# basic-maschinen.net
KiCad netlist of a schematic drawn in EAGLE
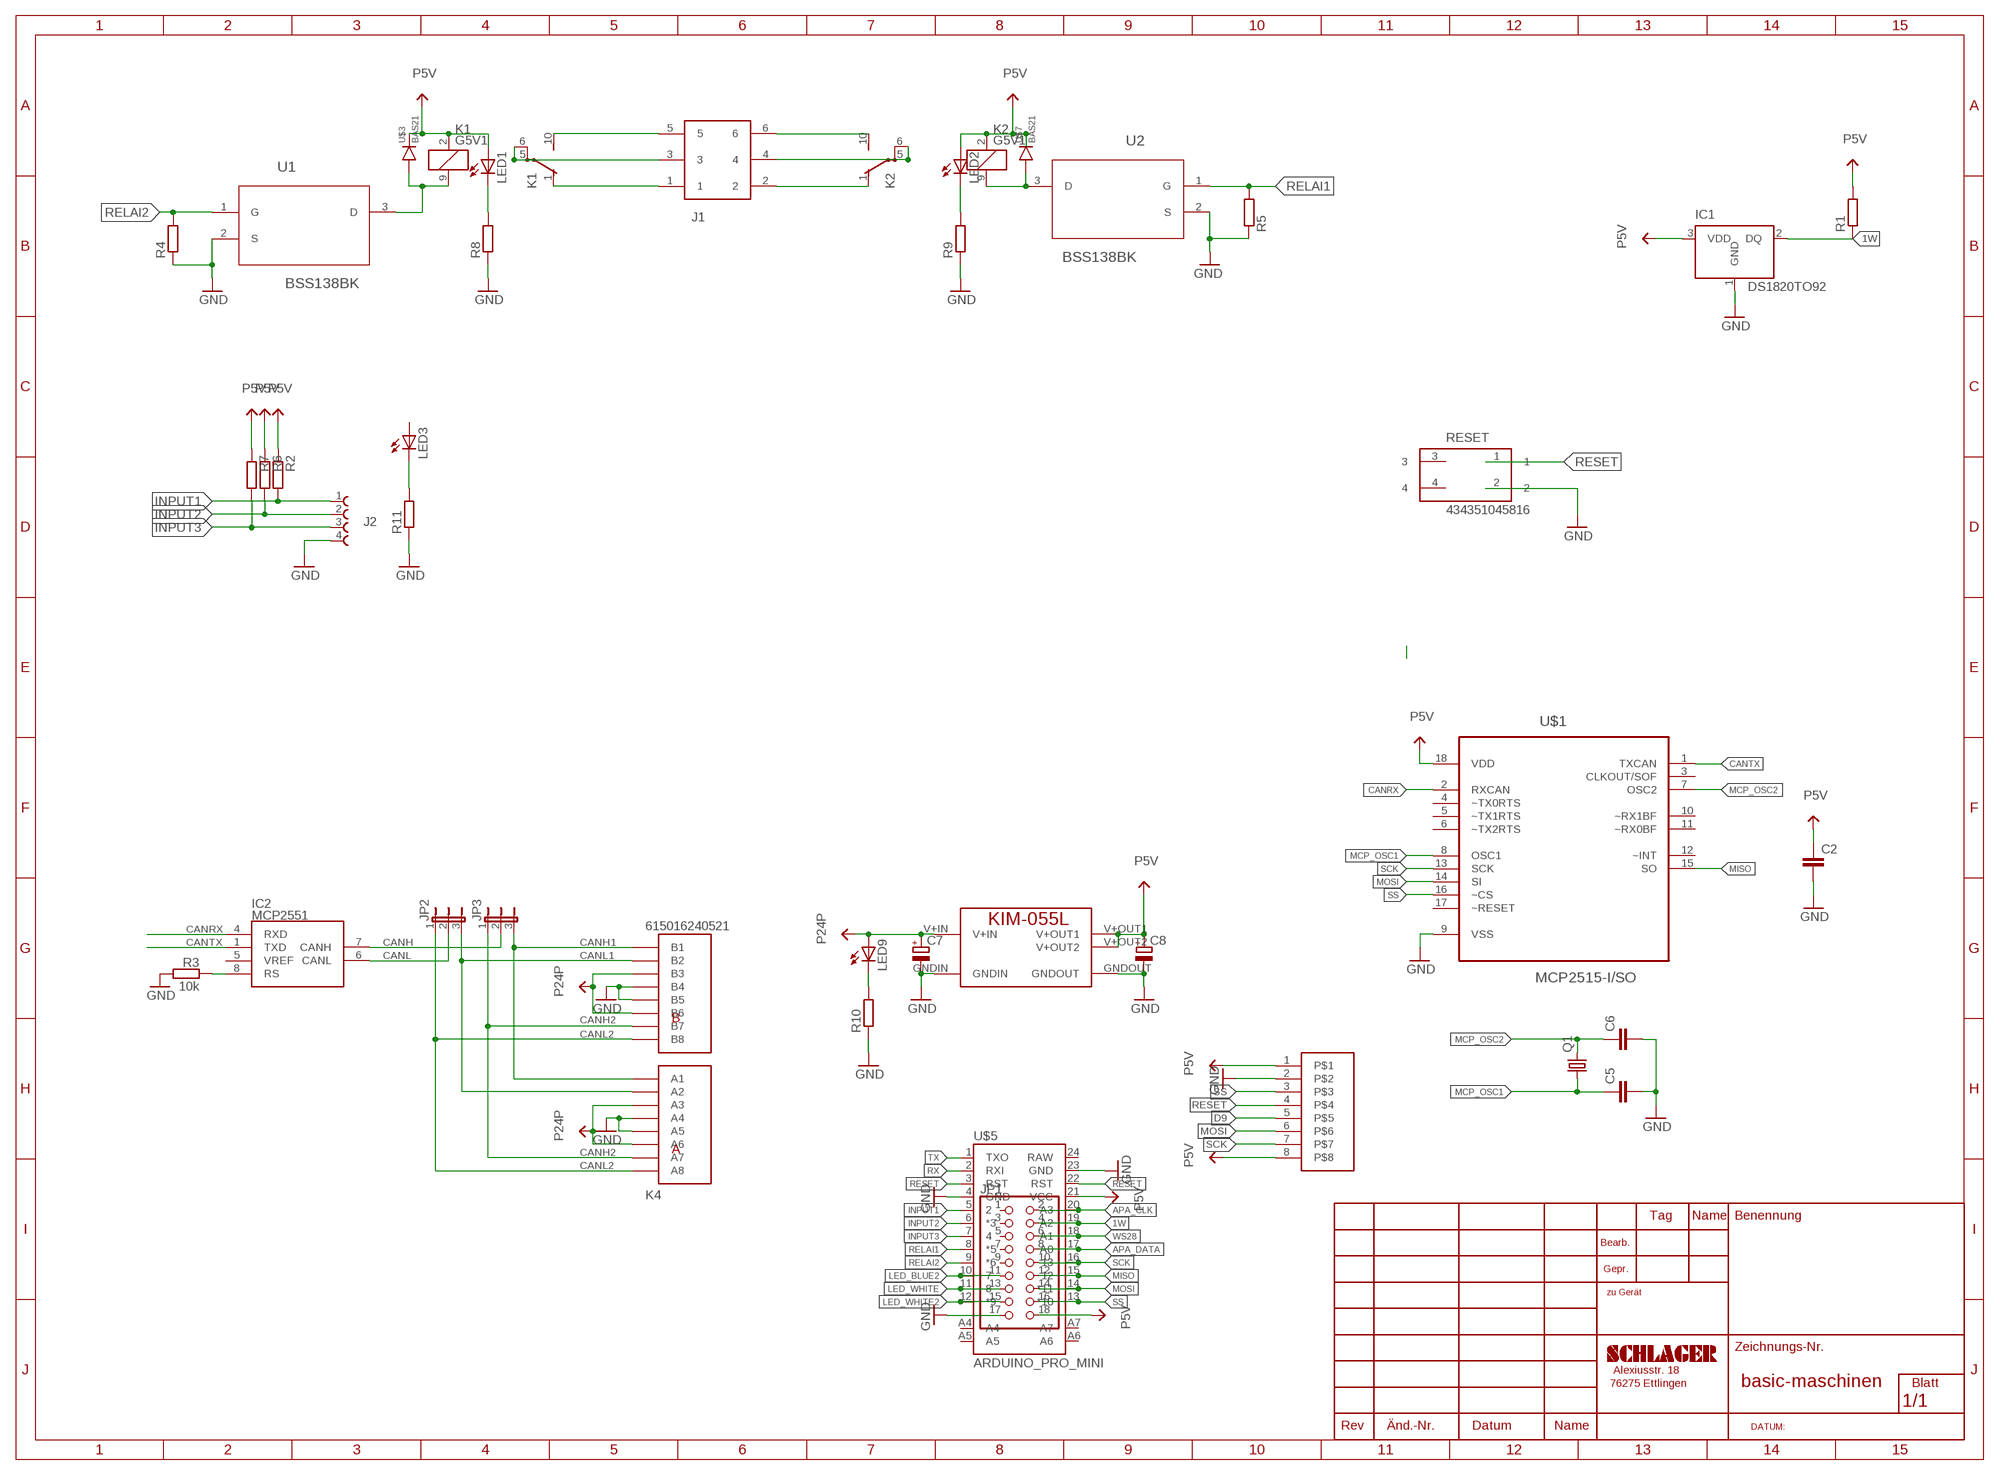
[diagram p0: schematic, sheet 1]

(export (version "E")
  (design (tool "Eeschema 10.0.6"))
  (components
    (comp (ref "C2")
      (value "C-EUC0805")
      (footprint "eagle-import:C0805")
      (libsource (lib "eagle-import") (part "C-EUC0805"))
    )
    (comp (ref "C5")
      (value "C-EUC0805")
      (footprint "eagle-import:C0805")
      (libsource (lib "eagle-import") (part "C-EUC0805"))
    )
    (comp (ref "C6")
      (value "C-EUC0805")
      (footprint "eagle-import:C0805")
      (libsource (lib "eagle-import") (part "C-EUC0805"))
    )
    (comp (ref "C7")
      (value "CPOL-EUE5-10.5")
      (footprint "eagle-import:E5-10,5")
      (libsource (lib "eagle-import") (part "CPOL-EUE5-10.5"))
    )
    (comp (ref "C8")
      (value "CPOL-EUE5-10.5")
      (footprint "eagle-import:E5-10,5")
      (libsource (lib "eagle-import") (part "CPOL-EUE5-10.5"))
    )
    (comp (ref "IC1")
      (value "DS1820TO92")
      (footprint "eagle-import:TO-92")
      (libsource (lib "eagle-import") (part "DS1820TO92"))
    )
    (comp (ref "IC2")
      (value "MCP2551")
      (footprint "eagle-import:SO-8")
      (libsource (lib "eagle-import") (part "MCP2551"))
    )
    (comp (ref "J1")
      (value "691327310006")
      (footprint "eagle-import:691327310006")
      (libsource (lib "eagle-import") (part "691327310006"))
    )
    (comp (ref "J2")
      (value "691322310004")
      (footprint "eagle-import:691322310004")
      (libsource (lib "eagle-import") (part "691322310004"))
    )
    (comp (ref "JP1")
      (value "PINHD-2X9")
      (footprint "eagle-import:2X09")
      (libsource (lib "eagle-import") (part "PINHD-2X9"))
    )
    (comp (ref "JP2")
      (value "JP2E")
      (footprint "eagle-import:JP2")
      (libsource (lib "eagle-import") (part "JP2E"))
    )
    (comp (ref "JP3")
      (value "JP2E")
      (footprint "eagle-import:JP2")
      (libsource (lib "eagle-import") (part "JP2E"))
    )
    (comp (ref "K1")
      (value "G5V1")
      (footprint "eagle-import:G5V1")
      (fields (field (name "MPN") "G5V-1-DC24"))
      (libsource (lib "eagle-import") (part "G5V1"))
    )
    (comp (ref "K2")
      (value "G5V1")
      (footprint "eagle-import:G5V1")
      (fields (field (name "MPN") "G5V-1-DC24"))
      (libsource (lib "eagle-import") (part "G5V1"))
    )
    (comp (ref "K4")
      (value "615016240521")
      (footprint "eagle-import:615016240521")
      (libsource (lib "eagle-import") (part "615016240521"))
    )
    (comp (ref "LED1")
      (value "LED3MM")
      (footprint "eagle-import:LED3MM")
      (libsource (lib "eagle-import") (part "LED3MM"))
    )
    (comp (ref "LED2")
      (value "LED3MM")
      (footprint "eagle-import:LED3MM")
      (libsource (lib "eagle-import") (part "LED3MM"))
    )
    (comp (ref "LED3")
      (value "LED3MM")
      (footprint "eagle-import:LED3MM")
      (libsource (lib "eagle-import") (part "LED3MM"))
    )
    (comp (ref "LED9")
      (value "LED3MM")
      (footprint "eagle-import:LED3MM")
      (libsource (lib "eagle-import") (part "LED3MM"))
    )
    (comp (ref "MOD1")
      (value "KIM-055L")
      (footprint "eagle-import:KIM-055L")
      (libsource (lib "eagle-import") (part "KIM-055L"))
    )
    (comp (ref "Q1")
      (value "CRYSTALHC49S")
      (footprint "eagle-import:HC49_S")
      (libsource (lib "eagle-import") (part "CRYSTALHC49S"))
    )
    (comp (ref "R1")
      (value "R-EU_M0805")
      (footprint "eagle-import:M0805")
      (libsource (lib "eagle-import") (part "schlager_passiv_R-EU_M0805"))
    )
    (comp (ref "R2")
      (value "R-EU_M0805")
      (footprint "eagle-import:M0805")
      (libsource (lib "eagle-import") (part "schlager_passiv_R-EU_M0805"))
    )
    (comp (ref "R3")
      (value "10k")
      (footprint "eagle-import:R0603")
      (libsource (lib "eagle-import") (part "R-EU_R0603"))
    )
    (comp (ref "R4")
      (value "R-EU_M0805")
      (footprint "eagle-import:M0805")
      (libsource (lib "eagle-import") (part "schlager_passiv_R-EU_M0805"))
    )
    (comp (ref "R5")
      (value "R-EU_M0805")
      (footprint "eagle-import:M0805")
      (libsource (lib "eagle-import") (part "schlager_passiv_R-EU_M0805"))
    )
    (comp (ref "R6")
      (value "R-EU_M0805")
      (footprint "eagle-import:M0805")
      (libsource (lib "eagle-import") (part "schlager_passiv_R-EU_M0805"))
    )
    (comp (ref "R7")
      (value "R-EU_M0805")
      (footprint "eagle-import:M0805")
      (libsource (lib "eagle-import") (part "schlager_passiv_R-EU_M0805"))
    )
    (comp (ref "R8")
      (value "R-EU_R0805")
      (footprint "eagle-import:R0805")
      (libsource (lib "eagle-import") (part "schlager_passiv_R-EU_R0805"))
    )
    (comp (ref "R9")
      (value "R-EU_R0805")
      (footprint "eagle-import:R0805")
      (libsource (lib "eagle-import") (part "schlager_passiv_R-EU_R0805"))
    )
    (comp (ref "R10")
      (value "R-EU_R0805")
      (footprint "eagle-import:R0805")
      (libsource (lib "eagle-import") (part "schlager_passiv_R-EU_R0805"))
    )
    (comp (ref "R11")
      (value "R-EU_R0805")
      (footprint "eagle-import:R0805")
      (libsource (lib "eagle-import") (part "schlager_passiv_R-EU_R0805"))
    )
    (comp (ref "RESET")
      (value "434351045816")
      (footprint "eagle-import:434351045816")
      (libsource (lib "eagle-import") (part "434351045816"))
    )
    (comp (ref "U$1")
      (value "MCP2515-I/SO")
      (footprint "eagle-import:SOIC127P1034X264-18N")
      (libsource (lib "eagle-import") (part "MCP2515-I/SO"))
    )
    (comp (ref "U$3")
      (value "BAS21")
      (footprint "eagle-import:SOT23")
      (libsource (lib "eagle-import") (part "BAS21"))
    )
    (comp (ref "U$4")
      (value "1.44-128X128")
      (footprint "eagle-import:1.44-128X128")
      (libsource (lib "eagle-import") (part "1.44-128X128"))
    )
    (comp (ref "U$5")
      (value "ARDUINO_PRO_MINI")
      (footprint "eagle-import:ARDUINO_PRO_MINI")
      (libsource (lib "eagle-import") (part "ARDUINO_PRO_MINI"))
    )
    (comp (ref "U$7")
      (value "BAS21")
      (footprint "eagle-import:SOT23")
      (libsource (lib "eagle-import") (part "BAS21"))
    )
    (comp (ref "U1")
      (value "BSS138BK")
      (footprint "eagle-import:SOT65P210X110-3N")
      (libsource (lib "eagle-import") (part "BSS138BK"))
    )
    (comp (ref "U2")
      (value "BSS138BK")
      (footprint "eagle-import:SOT65P210X110-3N")
      (libsource (lib "eagle-import") (part "BSS138BK"))
    )
  )
  (nets
    (net (code "1") (name "/CANH") (class "Default")
      (node (ref "IC2") (pin "7") (pinfunction "CANH_7") (pintype "bidirectional"))
      (node (ref "JP3") (pin "2") (pinfunction "2_2") (pintype "passive"))
    )
    (net (code "2") (name "/CANH1") (class "Default")
      (node (ref "JP3") (pin "3") (pinfunction "3_3") (pintype "passive"))
      (node (ref "K4") (pin "A1") (pinfunction "A1_A1") (pintype "passive"))
      (node (ref "K4") (pin "B1") (pinfunction "B1_B1") (pintype "passive"))
    )
    (net (code "3") (name "/CANH2") (class "Default")
      (node (ref "JP3") (pin "1") (pinfunction "1_1") (pintype "passive"))
      (node (ref "K4") (pin "A7") (pinfunction "A7_A7") (pintype "passive"))
      (node (ref "K4") (pin "B7") (pinfunction "B7_B7") (pintype "passive"))
    )
    (net (code "4") (name "/CANL") (class "Default")
      (node (ref "IC2") (pin "6") (pinfunction "CANL_6") (pintype "bidirectional"))
      (node (ref "JP2") (pin "2") (pinfunction "2_2") (pintype "passive"))
    )
    (net (code "5") (name "/CANL1") (class "Default")
      (node (ref "JP2") (pin "3") (pinfunction "3_3") (pintype "passive"))
      (node (ref "K4") (pin "A2") (pinfunction "A2_A2") (pintype "passive"))
      (node (ref "K4") (pin "B2") (pinfunction "B2_B2") (pintype "passive"))
    )
    (net (code "6") (name "/CANL2") (class "Default")
      (node (ref "JP2") (pin "1") (pinfunction "1_1") (pintype "passive"))
      (node (ref "K4") (pin "A8") (pinfunction "A8_A8") (pintype "passive"))
      (node (ref "K4") (pin "B8") (pinfunction "B8_B8") (pintype "passive"))
    )
    (net (code "7") (name "1W") (class "Default")
      (node (ref "IC1") (pin "2") (pinfunction "DQ_2") (pintype "output"))
      (node (ref "JP1") (pin "4") (pinfunction "4_4") (pintype "passive"))
      (node (ref "R1") (pin "1") (pinfunction "1_1") (pintype "passive"))
      (node (ref "U$5") (pin "19") (pinfunction "A2_19") (pintype "bidirectional"))
    )
    (net (code "8") (name "APA_CLK") (class "Default")
      (node (ref "JP1") (pin "2") (pinfunction "2_2") (pintype "passive"))
      (node (ref "U$5") (pin "20") (pinfunction "A3_20") (pintype "bidirectional"))
    )
    (net (code "9") (name "APA_DATA") (class "Default")
      (node (ref "JP1") (pin "8") (pinfunction "8_8") (pintype "passive"))
      (node (ref "U$5") (pin "17") (pinfunction "A0_17") (pintype "bidirectional"))
    )
    (net (code "10") (name "CANRX") (class "Default")
      (node (ref "IC2") (pin "4") (pinfunction "RXD_4") (pintype "bidirectional"))
      (node (ref "U$1") (pin "2") (pinfunction "RXCAN_2") (pintype "input"))
    )
    (net (code "11") (name "CANTX") (class "Default")
      (node (ref "IC2") (pin "1") (pinfunction "TXD_1") (pintype "bidirectional"))
      (node (ref "U$1") (pin "1") (pinfunction "TXCAN_1") (pintype "output"))
    )
    (net (code "12") (name "D9") (class "Default")
      (node (ref "U$4") (pin "5") (pinfunction "P$5_5") (pintype "bidirectional"))
    )
    (net (code "13") (name "GND") (class "Default")
      (node (ref "C2") (pin "2") (pinfunction "2_2") (pintype "passive"))
      (node (ref "C5") (pin "2") (pinfunction "2_2") (pintype "passive"))
      (node (ref "C6") (pin "2") (pinfunction "2_2") (pintype "passive"))
      (node (ref "C7") (pin "-") (pinfunction "-_-") (pintype "passive"))
      (node (ref "C8") (pin "-") (pinfunction "-_-") (pintype "passive"))
      (node (ref "IC1") (pin "1") (pinfunction "GND_1") (pintype "power_in"))
      (node (ref "J2") (pin "4") (pinfunction "4_4") (pintype "passive"))
      (node (ref "JP1") (pin "17") (pinfunction "17_17") (pintype "passive"))
      (node (ref "K4") (pin "A4") (pinfunction "A4_A4") (pintype "passive"))
      (node (ref "K4") (pin "A5") (pinfunction "A5_A5") (pintype "passive"))
      (node (ref "K4") (pin "B4") (pinfunction "B4_B4") (pintype "passive"))
      (node (ref "K4") (pin "B5") (pinfunction "B5_B5") (pintype "passive"))
      (node (ref "MOD1") (pin "GNDIN") (pinfunction "GNDIN_GNDIN") (pintype "bidirectional"))
      (node (ref "MOD1") (pin "GNDOUT") (pinfunction "GNDOUT_GNDOUT") (pintype "bidirectional"))
      (node (ref "R10") (pin "1") (pinfunction "1_1") (pintype "passive"))
      (node (ref "R11") (pin "1") (pinfunction "1_1") (pintype "passive"))
      (node (ref "R3") (pin "2") (pinfunction "2_2") (pintype "passive"))
      (node (ref "R4") (pin "1") (pinfunction "1_1") (pintype "passive"))
      (node (ref "R5") (pin "1") (pinfunction "1_1") (pintype "passive"))
      (node (ref "R8") (pin "1") (pinfunction "1_1") (pintype "passive"))
      (node (ref "R9") (pin "1") (pinfunction "1_1") (pintype "passive"))
      (node (ref "RESET") (pin "2") (pinfunction "2_2") (pintype "bidirectional"))
      (node (ref "U$1") (pin "9") (pinfunction "VSS_9") (pintype "power_in"))
      (node (ref "U$4") (pin "2") (pinfunction "P$2_2") (pintype "bidirectional"))
      (node (ref "U$5") (pin "23") (pinfunction "GND_23") (pintype "bidirectional"))
      (node (ref "U$5") (pin "4") (pinfunction "GND_4") (pintype "bidirectional"))
      (node (ref "U1") (pin "2") (pinfunction "S_2") (pintype "passive"))
      (node (ref "U2") (pin "2") (pinfunction "S_2") (pintype "passive"))
    )
    (net (code "14") (name "INPUT1") (class "Default")
      (node (ref "J2") (pin "1") (pinfunction "1_1") (pintype "passive"))
      (node (ref "R2") (pin "2") (pinfunction "2_2") (pintype "passive"))
      (node (ref "U$5") (pin "5") (pinfunction "2_5") (pintype "bidirectional"))
    )
    (net (code "15") (name "INPUT2") (class "Default")
      (node (ref "J2") (pin "2") (pinfunction "2_2") (pintype "passive"))
      (node (ref "R6") (pin "2") (pinfunction "2_2") (pintype "passive"))
      (node (ref "U$5") (pin "6") (pinfunction "*3_6") (pintype "bidirectional"))
    )
    (net (code "16") (name "INPUT3") (class "Default")
      (node (ref "J2") (pin "3") (pinfunction "3_3") (pintype "passive"))
      (node (ref "R7") (pin "2") (pinfunction "2_2") (pintype "passive"))
      (node (ref "U$5") (pin "7") (pinfunction "4_7") (pintype "bidirectional"))
    )
    (net (code "17") (name "LED_BLUE2") (class "Default")
      (node (ref "JP1") (pin "11") (pinfunction "11_11") (pintype "passive"))
      (node (ref "U$5") (pin "10") (pinfunction "7_10") (pintype "bidirectional"))
    )
    (net (code "18") (name "LED_WHITE") (class "Default")
      (node (ref "JP1") (pin "13") (pinfunction "13_13") (pintype "passive"))
      (node (ref "U$5") (pin "11") (pinfunction "8_11") (pintype "bidirectional"))
    )
    (net (code "19") (name "LED_WHITE2") (class "Default")
      (node (ref "JP1") (pin "15") (pinfunction "15_15") (pintype "passive"))
      (node (ref "U$5") (pin "12") (pinfunction "*9_12") (pintype "bidirectional"))
    )
    (net (code "20") (name "MCP_OSC1") (class "Default")
      (node (ref "C5") (pin "1") (pinfunction "1_1") (pintype "passive"))
      (node (ref "Q1") (pin "1") (pinfunction "1_1") (pintype "passive"))
      (node (ref "U$1") (pin "8") (pinfunction "OSC1_8") (pintype "input"))
    )
    (net (code "21") (name "MCP_OSC2") (class "Default")
      (node (ref "C6") (pin "1") (pinfunction "1_1") (pintype "passive"))
      (node (ref "Q1") (pin "2") (pinfunction "2_2") (pintype "passive"))
      (node (ref "U$1") (pin "7") (pinfunction "OSC2_7") (pintype "output"))
    )
    (net (code "22") (name "MISO") (class "Default")
      (node (ref "JP1") (pin "12") (pinfunction "12_12") (pintype "passive"))
      (node (ref "U$1") (pin "15") (pinfunction "SO_15") (pintype "output"))
      (node (ref "U$5") (pin "15") (pinfunction "12_15") (pintype "bidirectional"))
    )
    (net (code "23") (name "MOSI") (class "Default")
      (node (ref "JP1") (pin "14") (pinfunction "14_14") (pintype "passive"))
      (node (ref "U$1") (pin "14") (pinfunction "SI_14") (pintype "input"))
      (node (ref "U$4") (pin "6") (pinfunction "P$6_6") (pintype "bidirectional"))
      (node (ref "U$5") (pin "14") (pinfunction "*11_14") (pintype "bidirectional"))
    )
    (net (code "24") (name "Net-(IC2A-RS)") (class "Default")
      (node (ref "IC2") (pin "8") (pinfunction "RS_8") (pintype "bidirectional"))
      (node (ref "R3") (pin "1") (pinfunction "1_1") (pintype "passive"))
    )
    (net (code "25") (name "Net-(J1-Pad3)") (class "Default")
      (node (ref "J1") (pin "3") (pinfunction "3_3") (pintype "passive"))
      (node (ref "K1") (pin "5") (pinfunction "P_5") (pintype "passive"))
      (node (ref "K1") (pin "6") (pinfunction "P_6") (pintype "passive"))
    )
    (net (code "26") (name "Net-(J1-Pad4)") (class "Default")
      (node (ref "J1") (pin "4") (pinfunction "4_4") (pintype "passive"))
      (node (ref "K2") (pin "5") (pinfunction "P_5") (pintype "passive"))
      (node (ref "K2") (pin "6") (pinfunction "P_6") (pintype "passive"))
    )
    (net (code "27") (name "Net-(K1A-2)") (class "Default")
      (node (ref "K1") (pin "9") (pinfunction "2_9") (pintype "passive"))
      (node (ref "U$3") (pin "1") (pinfunction "A_1") (pintype "bidirectional"))
      (node (ref "U1") (pin "3") (pinfunction "D_3") (pintype "passive"))
    )
    (net (code "28") (name "Net-(K1B-O)") (class "Default")
      (node (ref "J1") (pin "1") (pinfunction "1_1") (pintype "passive"))
      (node (ref "K1") (pin "1") (pinfunction "O_1") (pintype "passive"))
    )
    (net (code "29") (name "Net-(K1B-S)") (class "Default")
      (node (ref "J1") (pin "5") (pinfunction "5_5") (pintype "passive"))
      (node (ref "K1") (pin "10") (pinfunction "S_10") (pintype "passive"))
    )
    (net (code "30") (name "Net-(K2A-2)") (class "Default")
      (node (ref "K2") (pin "9") (pinfunction "2_9") (pintype "passive"))
      (node (ref "U$7") (pin "1") (pinfunction "A_1") (pintype "bidirectional"))
      (node (ref "U2") (pin "3") (pinfunction "D_3") (pintype "passive"))
    )
    (net (code "31") (name "Net-(K2B-O)") (class "Default")
      (node (ref "J1") (pin "2") (pinfunction "2_2") (pintype "passive"))
      (node (ref "K2") (pin "1") (pinfunction "O_1") (pintype "passive"))
    )
    (net (code "32") (name "Net-(K2B-S)") (class "Default")
      (node (ref "J1") (pin "6") (pinfunction "6_6") (pintype "passive"))
      (node (ref "K2") (pin "10") (pinfunction "S_10") (pintype "passive"))
    )
    (net (code "33") (name "Net-(LED1-C)") (class "Default")
      (node (ref "LED1") (pin "K") (pinfunction "C_K") (pintype "passive"))
      (node (ref "R8") (pin "2") (pinfunction "2_2") (pintype "passive"))
    )
    (net (code "34") (name "Net-(LED2-C)") (class "Default")
      (node (ref "LED2") (pin "K") (pinfunction "C_K") (pintype "passive"))
      (node (ref "R9") (pin "2") (pinfunction "2_2") (pintype "passive"))
    )
    (net (code "35") (name "Net-(LED3-C)") (class "Default")
      (node (ref "LED3") (pin "K") (pinfunction "C_K") (pintype "passive"))
      (node (ref "R11") (pin "2") (pinfunction "2_2") (pintype "passive"))
    )
    (net (code "36") (name "Net-(LED9-C)") (class "Default")
      (node (ref "LED9") (pin "K") (pinfunction "C_K") (pintype "passive"))
      (node (ref "R10") (pin "2") (pinfunction "2_2") (pintype "passive"))
    )
    (net (code "37") (name "P5V") (class "Default")
      (node (ref "C2") (pin "1") (pinfunction "1_1") (pintype "passive"))
      (node (ref "C8") (pin "+") (pinfunction "+_+") (pintype "passive"))
      (node (ref "IC1") (pin "3") (pinfunction "VDD_3") (pintype "input"))
      (node (ref "JP1") (pin "18") (pinfunction "18_18") (pintype "passive"))
      (node (ref "K1") (pin "2") (pinfunction "1_2") (pintype "passive"))
      (node (ref "K2") (pin "2") (pinfunction "1_2") (pintype "passive"))
      (node (ref "LED1") (pin "A") (pinfunction "A_A") (pintype "passive"))
      (node (ref "LED2") (pin "A") (pinfunction "A_A") (pintype "passive"))
      (node (ref "MOD1") (pin "V+OUT1") (pinfunction "V+OUT1_V+OUT1") (pintype "bidirectional"))
      (node (ref "MOD1") (pin "V+OUT2") (pinfunction "V+OUT2_V+OUT2") (pintype "bidirectional"))
      (node (ref "R1") (pin "2") (pinfunction "2_2") (pintype "passive"))
      (node (ref "R2") (pin "1") (pinfunction "1_1") (pintype "passive"))
      (node (ref "R6") (pin "1") (pinfunction "1_1") (pintype "passive"))
      (node (ref "R7") (pin "1") (pinfunction "1_1") (pintype "passive"))
      (node (ref "U$1") (pin "18") (pinfunction "VDD_18") (pintype "power_in"))
      (node (ref "U$3") (pin "3") (pinfunction "C_3") (pintype "bidirectional"))
      (node (ref "U$4") (pin "1") (pinfunction "P$1_1") (pintype "bidirectional"))
      (node (ref "U$4") (pin "8") (pinfunction "P$8_8") (pintype "bidirectional"))
      (node (ref "U$5") (pin "21") (pinfunction "VCC_21") (pintype "bidirectional"))
      (node (ref "U$7") (pin "3") (pinfunction "C_3") (pintype "bidirectional"))
    )
    (net (code "38") (name "P24P") (class "Default")
      (node (ref "C7") (pin "+") (pinfunction "+_+") (pintype "passive"))
      (node (ref "K4") (pin "A3") (pinfunction "A3_A3") (pintype "passive"))
      (node (ref "K4") (pin "A6") (pinfunction "A6_A6") (pintype "passive"))
      (node (ref "K4") (pin "B3") (pinfunction "B3_B3") (pintype "passive"))
      (node (ref "K4") (pin "B6") (pinfunction "B6_B6") (pintype "passive"))
      (node (ref "LED9") (pin "A") (pinfunction "A_A") (pintype "passive"))
      (node (ref "MOD1") (pin "V+IN") (pinfunction "V+IN_V+IN") (pintype "bidirectional"))
    )
    (net (code "39") (name "RELAI1") (class "Default")
      (node (ref "R5") (pin "2") (pinfunction "2_2") (pintype "passive"))
      (node (ref "U$5") (pin "8") (pinfunction "*5_8") (pintype "bidirectional"))
      (node (ref "U2") (pin "1") (pinfunction "G_1") (pintype "passive"))
    )
    (net (code "40") (name "RELAI2") (class "Default")
      (node (ref "R4") (pin "2") (pinfunction "2_2") (pintype "passive"))
      (node (ref "U$5") (pin "9") (pinfunction "*6_9") (pintype "bidirectional"))
      (node (ref "U1") (pin "1") (pinfunction "G_1") (pintype "passive"))
    )
    (net (code "41") (name "RESET") (class "Default")
      (node (ref "RESET") (pin "1") (pinfunction "1_1") (pintype "bidirectional"))
      (node (ref "U$4") (pin "4") (pinfunction "P$4_4") (pintype "bidirectional"))
      (node (ref "U$5") (pin "22") (pinfunction "RST_22") (pintype "bidirectional"))
      (node (ref "U$5") (pin "3") (pinfunction "RST_3") (pintype "bidirectional"))
    )
    (net (code "42") (name "RX") (class "Default")
      (node (ref "U$5") (pin "2") (pinfunction "RXI_2") (pintype "bidirectional"))
    )
    (net (code "43") (name "SCK") (class "Default")
      (node (ref "JP1") (pin "10") (pinfunction "10_10") (pintype "passive"))
      (node (ref "U$1") (pin "13") (pinfunction "SCK_13") (pintype "input"))
      (node (ref "U$4") (pin "7") (pinfunction "P$7_7") (pintype "bidirectional"))
      (node (ref "U$5") (pin "16") (pinfunction "13_16") (pintype "bidirectional"))
    )
    (net (code "44") (name "SS") (class "Default")
      (node (ref "JP1") (pin "16") (pinfunction "16_16") (pintype "passive"))
      (node (ref "U$1") (pin "16") (pinfunction "~{CS}_16") (pintype "input"))
      (node (ref "U$4") (pin "3") (pinfunction "P$3_3") (pintype "bidirectional"))
      (node (ref "U$5") (pin "13") (pinfunction "*10_13") (pintype "bidirectional"))
    )
    (net (code "45") (name "TX") (class "Default")
      (node (ref "U$5") (pin "1") (pinfunction "TXO_1") (pintype "bidirectional"))
    )
    (net (code "46") (name "WS28") (class "Default")
      (node (ref "JP1") (pin "6") (pinfunction "6_6") (pintype "passive"))
      (node (ref "U$5") (pin "18") (pinfunction "A1_18") (pintype "bidirectional"))
    )
    (net (code "47") (name "unconnected-(IC2A-VREF-Pad5)") (class "Default")
      (node (ref "IC2") (pin "5") (pinfunction "VREF_5") (pintype "bidirectional"))
    )
    (net (code "48") (name "unconnected-(JP1-Pad1)") (class "Default")
      (node (ref "JP1") (pin "1") (pinfunction "1_1") (pintype "passive"))
    )
    (net (code "49") (name "unconnected-(JP1-Pad3)") (class "Default")
      (node (ref "JP1") (pin "3") (pinfunction "3_3") (pintype "passive"))
    )
    (net (code "50") (name "unconnected-(JP1-Pad5)") (class "Default")
      (node (ref "JP1") (pin "5") (pinfunction "5_5") (pintype "passive"))
    )
    (net (code "51") (name "unconnected-(JP1-Pad7)") (class "Default")
      (node (ref "JP1") (pin "7") (pinfunction "7_7") (pintype "passive"))
    )
    (net (code "52") (name "unconnected-(JP1-Pad9)") (class "Default")
      (node (ref "JP1") (pin "9") (pinfunction "9_9") (pintype "passive"))
    )
    (net (code "53") (name "unconnected-(LED3-PadA)") (class "Default")
      (node (ref "LED3") (pin "A") (pinfunction "A_A") (pintype "passive"))
    )
    (net (code "54") (name "unconnected-(RESET-Pad3)") (class "Default")
      (node (ref "RESET") (pin "3") (pinfunction "3_3") (pintype "bidirectional"))
    )
    (net (code "55") (name "unconnected-(RESET-Pad4)") (class "Default")
      (node (ref "RESET") (pin "4") (pinfunction "4_4") (pintype "bidirectional"))
    )
    (net (code "56") (name "unconnected-(U$1-CLKOUT{slash}SOF-Pad3)") (class "Default")
      (node (ref "U$1") (pin "3") (pinfunction "CLKOUT/SOF_3") (pintype "output"))
    )
    (net (code "57") (name "unconnected-(U$1-~{INT}-Pad12)") (class "Default")
      (node (ref "U$1") (pin "12") (pinfunction "~{INT}_12") (pintype "output"))
    )
    (net (code "58") (name "unconnected-(U$1-~{RESET}-Pad17)") (class "Default")
      (node (ref "U$1") (pin "17") (pinfunction "~{RESET}_17") (pintype "input"))
    )
    (net (code "59") (name "unconnected-(U$1-~{RX0BF}-Pad11)") (class "Default")
      (node (ref "U$1") (pin "11") (pinfunction "~{RX0BF}_11") (pintype "output"))
    )
    (net (code "60") (name "unconnected-(U$1-~{RX1BF}-Pad10)") (class "Default")
      (node (ref "U$1") (pin "10") (pinfunction "~{RX1BF}_10") (pintype "output"))
    )
    (net (code "61") (name "unconnected-(U$1-~{TX0RTS}-Pad4)") (class "Default")
      (node (ref "U$1") (pin "4") (pinfunction "~{TX0RTS}_4") (pintype "input"))
    )
    (net (code "62") (name "unconnected-(U$1-~{TX1RTS}-Pad5)") (class "Default")
      (node (ref "U$1") (pin "5") (pinfunction "~{TX1RTS}_5") (pintype "input"))
    )
    (net (code "63") (name "unconnected-(U$1-~{TX2RTS}-Pad6)") (class "Default")
      (node (ref "U$1") (pin "6") (pinfunction "~{TX2RTS}_6") (pintype "input"))
    )
    (net (code "64") (name "unconnected-(U$5-PadA4)") (class "Default")
      (node (ref "U$5") (pin "A4") (pinfunction "A4_A4") (pintype "bidirectional"))
    )
    (net (code "65") (name "unconnected-(U$5-PadA5)") (class "Default")
      (node (ref "U$5") (pin "A5") (pinfunction "A5_A5") (pintype "bidirectional"))
    )
    (net (code "66") (name "unconnected-(U$5-PadA6)") (class "Default")
      (node (ref "U$5") (pin "A6") (pinfunction "A6_A6") (pintype "bidirectional"))
    )
    (net (code "67") (name "unconnected-(U$5-PadA7)") (class "Default")
      (node (ref "U$5") (pin "A7") (pinfunction "A7_A7") (pintype "bidirectional"))
    )
    (net (code "68") (name "unconnected-(U$5-RAW-Pad24)") (class "Default")
      (node (ref "U$5") (pin "24") (pinfunction "RAW_24") (pintype "bidirectional"))
    )
  )
)
